# ETH_PCIE_PHY.net
KiCad netlist of a schematic drawn in Altium Designer
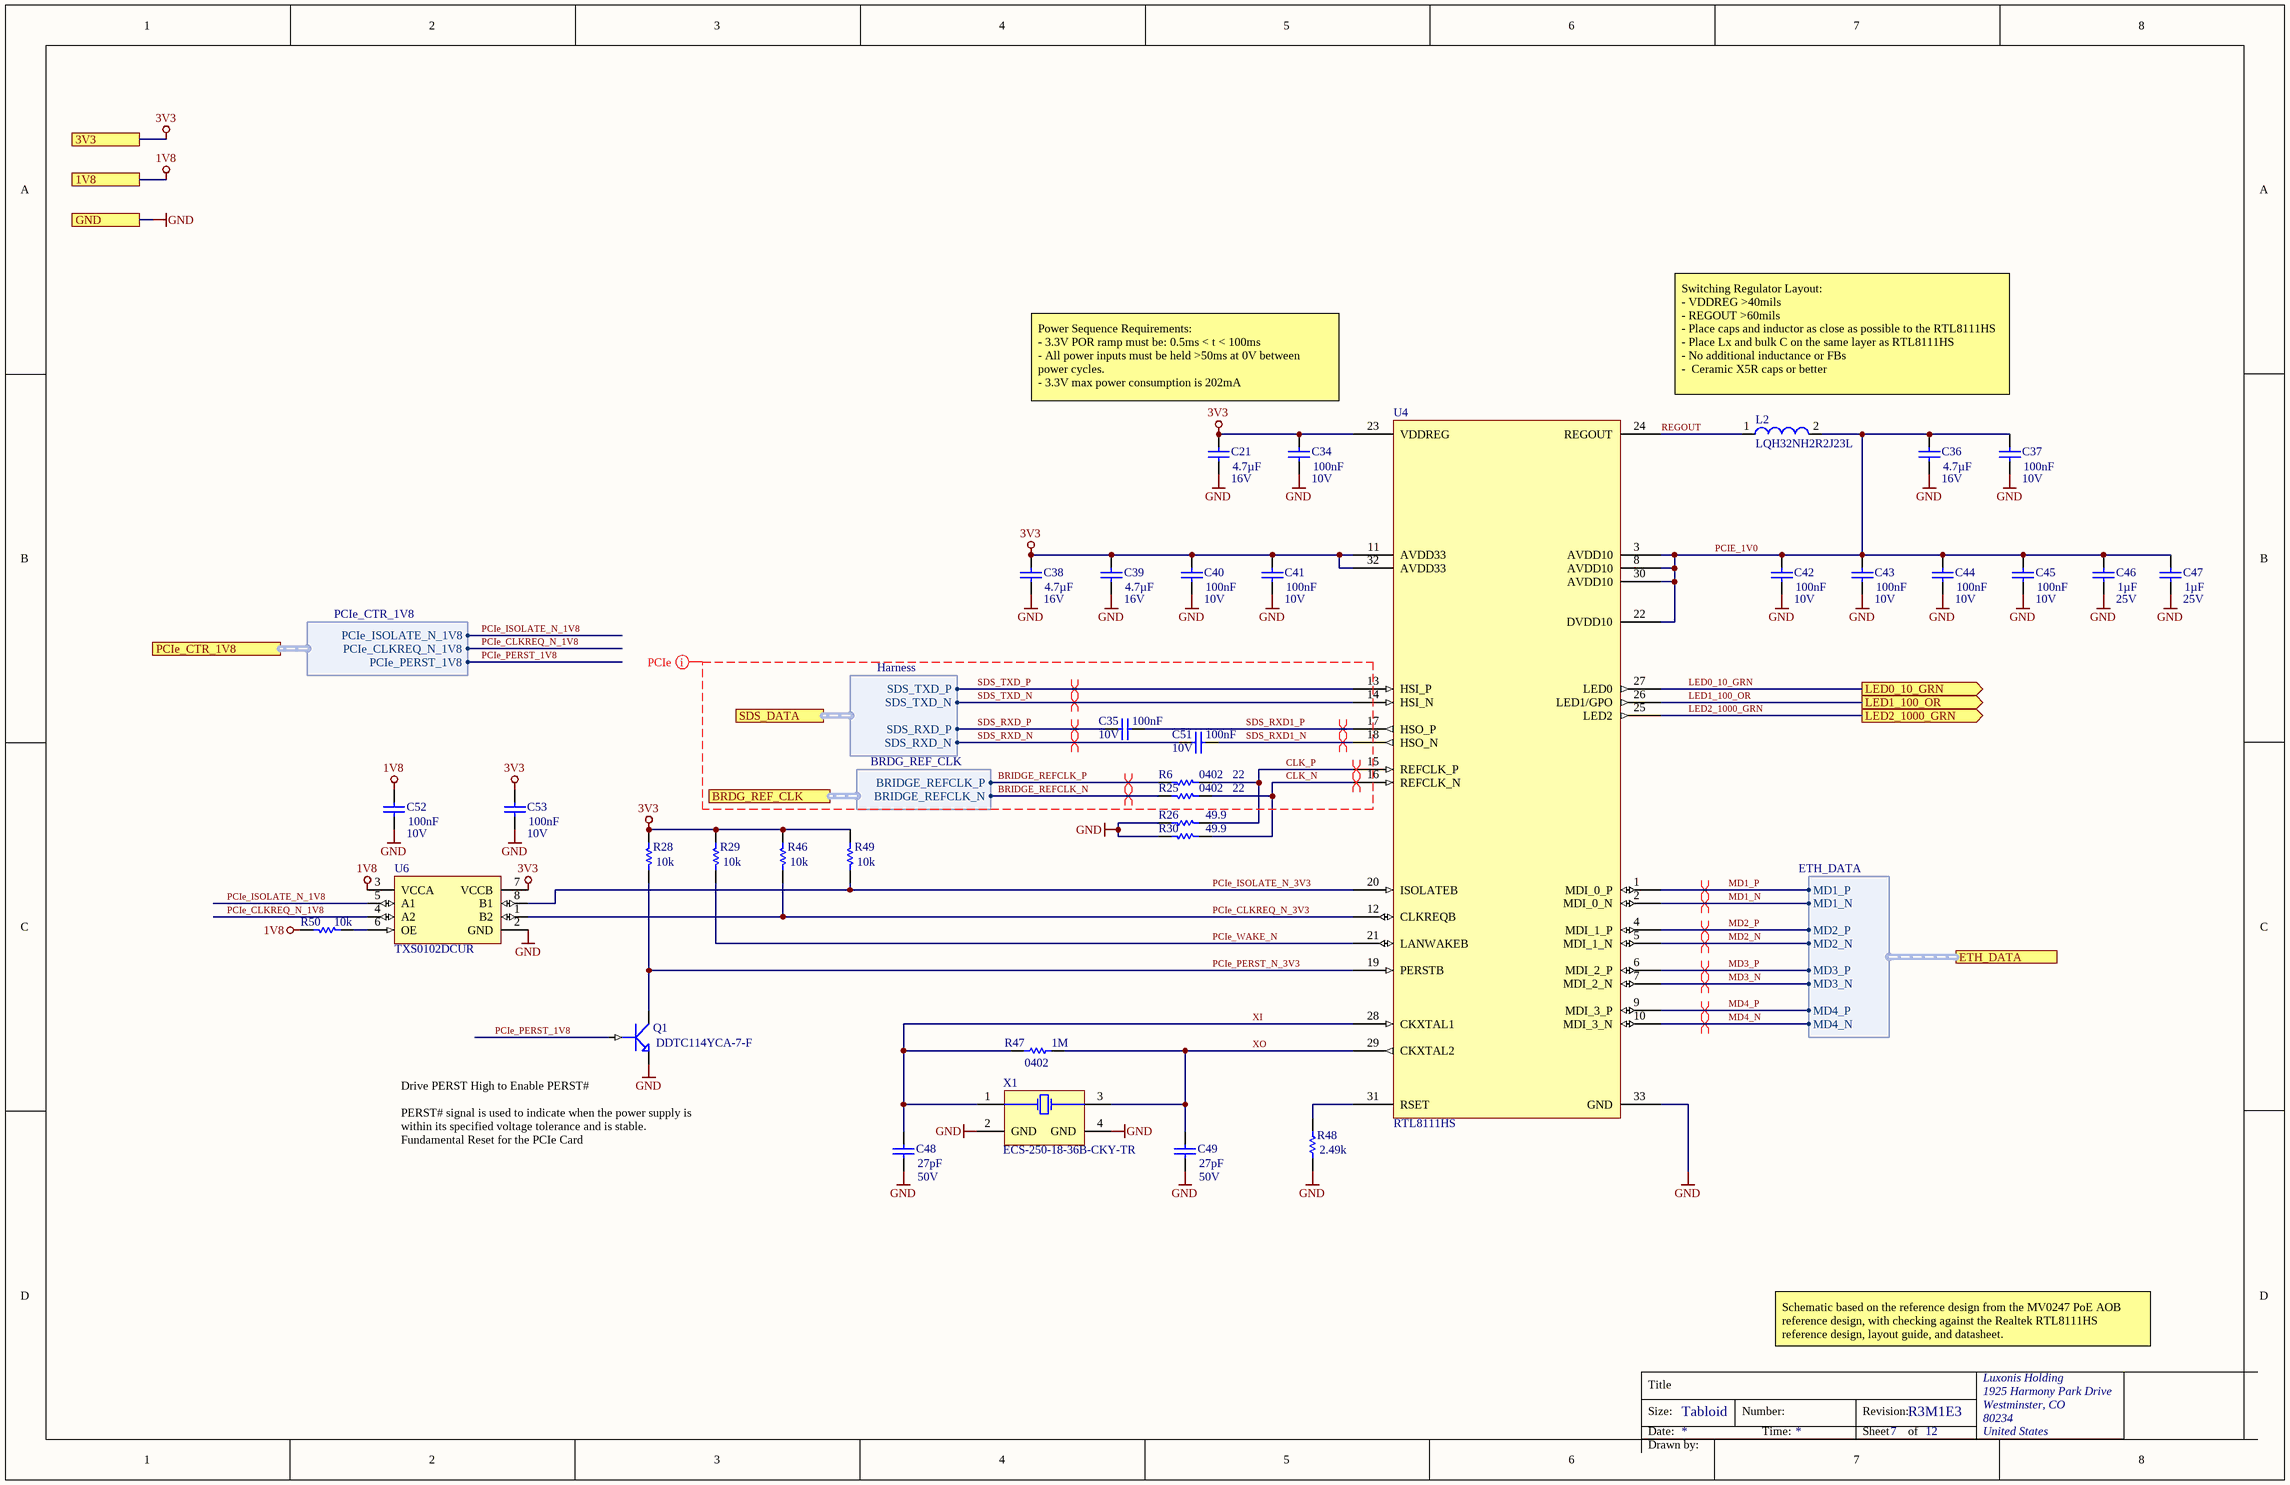
[diagram p0: ETH_PCIE_PHY.SchDoc]

(export (version "E")
  (design (tool "Eeschema 10.0.6"))
  (components
    (comp (ref "C21")
      (value "4.7µF")
      (footprint "CAPC0603(1608)100_N")
      (description "CAP CER 4.7UF 16V X5R 0603 10%")
      (fields
        (field (name "TOLERANCE") "10%")
        (field (name "VOLTAGE RATING") "16V")
        (field (name "Comment") "GRM188R61C475KAAJD")
      )
      (libsource (lib "Luxonis LLC") (part "LLL153C70G474ME17E"))
    )
    (comp (ref "C34")
      (value "100nF")
      (footprint "CAPC0402(1005)70_N")
      (description "CAP CER 0.1UF 10V X7R 0402 5%")
      (fields
        (field (name "TOLERANCE") "5%")
        (field (name "VOLTAGE RATING") "10V")
        (field (name "Comment") "GRM155R71A104JA01D")
      )
      (libsource (lib "Luxonis LLC") (part "GRM188R61C475KAAJD"))
    )
    (comp (ref "C35")
      (value "100nF")
      (footprint "CAPC0201(0603)33_L")
      (description "CAP CER 0.1UF 10V X5R 0201 10%")
      (fields
        (field (name "TOLERANCE") "10%")
        (field (name "VOLTAGE RATING") "10V")
        (field (name "Comment") "GRM033R61A104KE15D")
      )
      (libsource (lib "Luxonis LLC") (part "LLL153C70G474ME17E"))
    )
    (comp (ref "C36")
      (value "4.7µF")
      (footprint "CAPC0603(1608)100_N")
      (description "CAP CER 4.7UF 16V X5R 0603 10%")
      (fields
        (field (name "TOLERANCE") "10%")
        (field (name "VOLTAGE RATING") "16V")
        (field (name "Comment") "GRM188R61C475KAAJD")
      )
      (libsource (lib "Luxonis LLC") (part "LLL153C70G474ME17E"))
    )
    (comp (ref "C37")
      (value "100nF")
      (footprint "CAPC0402(1005)70_N")
      (description "CAP CER 0.1UF 10V X7R 0402 5%")
      (fields
        (field (name "TOLERANCE") "5%")
        (field (name "VOLTAGE RATING") "10V")
        (field (name "Comment") "GRM155R71A104JA01D")
      )
      (libsource (lib "Luxonis LLC") (part "GRM188R61C475KAAJD"))
    )
    (comp (ref "C38")
      (value "4.7µF")
      (footprint "CAPC0603(1608)100_N")
      (description "CAP CER 4.7UF 16V X5R 0603 10%")
      (fields
        (field (name "TOLERANCE") "10%")
        (field (name "VOLTAGE RATING") "16V")
        (field (name "Comment") "GRM188R61C475KAAJD")
      )
      (libsource (lib "Luxonis LLC") (part "LLL153C70G474ME17E"))
    )
    (comp (ref "C39")
      (value "4.7µF")
      (footprint "CAPC0603(1608)100_N")
      (description "CAP CER 4.7UF 16V X5R 0603 10%")
      (fields
        (field (name "TOLERANCE") "10%")
        (field (name "VOLTAGE RATING") "16V")
        (field (name "Comment") "GRM188R61C475KAAJD")
      )
      (libsource (lib "Luxonis LLC") (part "LLL153C70G474ME17E"))
    )
    (comp (ref "C40")
      (value "100nF")
      (footprint "CAPC0402(1005)70_N")
      (description "CAP CER 0.1UF 10V X7R 0402 5%")
      (fields
        (field (name "TOLERANCE") "5%")
        (field (name "VOLTAGE RATING") "10V")
        (field (name "Comment") "GRM155R71A104JA01D")
      )
      (libsource (lib "Luxonis LLC") (part "GRM188R61C475KAAJD"))
    )
    (comp (ref "C41")
      (value "100nF")
      (footprint "CAPC0402(1005)70_N")
      (description "CAP CER 0.1UF 10V X7R 0402 5%")
      (fields
        (field (name "TOLERANCE") "5%")
        (field (name "VOLTAGE RATING") "10V")
        (field (name "Comment") "GRM155R71A104JA01D")
      )
      (libsource (lib "Luxonis LLC") (part "GRM188R61C475KAAJD"))
    )
    (comp (ref "C42")
      (value "100nF")
      (footprint "CAPC0402(1005)70_N")
      (description "CAP CER 0.1UF 10V X7R 0402 5%")
      (fields
        (field (name "TOLERANCE") "5%")
        (field (name "VOLTAGE RATING") "10V")
        (field (name "Comment") "GRM155R71A104JA01D")
      )
      (libsource (lib "Luxonis LLC") (part "GRM188R61C475KAAJD"))
    )
    (comp (ref "C43")
      (value "100nF")
      (footprint "CAPC0402(1005)70_N")
      (description "CAP CER 0.1UF 10V X7R 0402 5%")
      (fields
        (field (name "TOLERANCE") "5%")
        (field (name "VOLTAGE RATING") "10V")
        (field (name "Comment") "GRM155R71A104JA01D")
      )
      (libsource (lib "Luxonis LLC") (part "GRM188R61C475KAAJD"))
    )
    (comp (ref "C44")
      (value "100nF")
      (footprint "CAPC0402(1005)70_N")
      (description "CAP CER 0.1UF 10V X7R 0402 5%")
      (fields
        (field (name "TOLERANCE") "5%")
        (field (name "VOLTAGE RATING") "10V")
        (field (name "Comment") "GRM155R71A104JA01D")
      )
      (libsource (lib "Luxonis LLC") (part "GRM188R61C475KAAJD"))
    )
    (comp (ref "C45")
      (value "100nF")
      (footprint "CAPC0402(1005)70_N")
      (description "CAP CER 0.1UF 10V X7R 0402 5%")
      (fields
        (field (name "TOLERANCE") "5%")
        (field (name "VOLTAGE RATING") "10V")
        (field (name "Comment") "GRM155R71A104JA01D")
      )
      (libsource (lib "Luxonis LLC") (part "GRM188R61C475KAAJD"))
    )
    (comp (ref "C46")
      (value "1µF")
      (footprint "CAPC0402(1005)70_N")
      (description "CAP CER 1UF 25V X5R 0402 10%")
      (fields
        (field (name "TOLERANCE") "10%")
        (field (name "VOLTAGE RATING") "25V")
        (field (name "Comment") "GRM155R61E105KA12D")
      )
      (libsource (lib "Luxonis LLC") (part "GRM188R61C475KAAJD"))
    )
    (comp (ref "C47")
      (value "1µF")
      (footprint "CAPC0402(1005)70_N")
      (description "CAP CER 1UF 25V X5R 0402 10%")
      (fields
        (field (name "TOLERANCE") "10%")
        (field (name "VOLTAGE RATING") "25V")
        (field (name "Comment") "GRM155R61E105KA12D")
      )
      (libsource (lib "Luxonis LLC") (part "GRM188R61C475KAAJD"))
    )
    (comp (ref "C48")
      (value "27pF")
      (footprint "CAPC0402(1005)60_N")
      (description "CAP CER 27PF 50V C0G 0402 5%")
      (fields
        (field (name "TOLERANCE") "5%")
        (field (name "VOLTAGE RATING") "50V")
        (field (name "Comment") "C0402C270J5GACTU")
      )
      (libsource (lib "Luxonis LLC") (part "GRM188R61C475KAAJD"))
    )
    (comp (ref "C49")
      (value "27pF")
      (footprint "CAPC0402(1005)60_N")
      (description "CAP CER 27PF 50V C0G 0402 5%")
      (fields
        (field (name "TOLERANCE") "5%")
        (field (name "VOLTAGE RATING") "50V")
        (field (name "Comment") "C0402C270J5GACTU")
      )
      (libsource (lib "Luxonis LLC") (part "GRM188R61C475KAAJD"))
    )
    (comp (ref "C51")
      (value "100nF")
      (footprint "CAPC0201(0603)33_L")
      (description "CAP CER 0.1UF 10V X5R 0201 10%")
      (fields
        (field (name "TOLERANCE") "10%")
        (field (name "VOLTAGE RATING") "10V")
        (field (name "Comment") "GRM033R61A104KE15D")
      )
      (libsource (lib "Luxonis LLC") (part "LLL153C70G474ME17E"))
    )
    (comp (ref "C52")
      (value "100nF")
      (footprint "CAPC0402(1005)70_N")
      (description "CAP CER 0.1UF 10V X7R 0402 5%")
      (fields
        (field (name "TOLERANCE") "5%")
        (field (name "VOLTAGE RATING") "10V")
        (field (name "Comment") "GRM155R71A104JA01D")
      )
      (libsource (lib "Luxonis LLC") (part "GRM188R61C475KAAJD"))
    )
    (comp (ref "C53")
      (value "100nF")
      (footprint "CAPC0402(1005)70_N")
      (description "CAP CER 0.1UF 10V X7R 0402 5%")
      (fields
        (field (name "TOLERANCE") "5%")
        (field (name "VOLTAGE RATING") "10V")
        (field (name "Comment") "GRM155R71A104JA01D")
      )
      (libsource (lib "Luxonis LLC") (part "GRM188R61C475KAAJD"))
    )
    (comp (ref "L2")
      (value "LQH32NH2R2J23L")
      (footprint "LQH32NH2R2J23L")
      (description "FIXED IND 2.2UH 610MA 97MOHM SMD")
      (fields (field (name "TOLERANCE") "5%"))
      (libsource (lib "Luxonis LLC") (part "DFE252012P-1R0M=P2"))
    )
    (comp (ref "Q1")
      (value "DDTC114YCA-7-F")
      (footprint "DDTC114YCA-7-F-Footprint-1")
      (description "TRANS PREBIAS NPN 200MW SOT23-3")
      (libsource (lib "Luxonis LLC") (part "DDTC114YCA-7-F"))
    )
    (comp (ref "R6")
      (value "22")
      (footprint "RESC0402(1005)_L")
      (description "RES SMD 22 OHM 1% 1/16W 0402")
      (fields
        (field (name "CASE/PACKAGE") "0402")
        (field (name "TOLERANCE") "1%")
        (field (name "Comment") "RC0402FR-0722RL")
      )
      (libsource (lib "Luxonis LLC") (part "Default resistor symbol"))
    )
    (comp (ref "R25")
      (value "22")
      (footprint "RESC0402(1005)_L")
      (description "RES SMD 22 OHM 1% 1/16W 0402")
      (fields
        (field (name "CASE/PACKAGE") "0402")
        (field (name "TOLERANCE") "1%")
        (field (name "Comment") "RC0402FR-0722RL")
      )
      (libsource (lib "Luxonis LLC") (part "Default resistor symbol"))
    )
    (comp (ref "R26")
      (value "49.9")
      (footprint "RESC0402(1005)_L")
      (description "RES SMD 49.9 OHM 1% 1/16W 0402")
      (fields (field (name "TOLERANCE") "1%") (field (name "Comment") "RC0402FR-0749R9L"))
      (libsource (lib "Luxonis LLC") (part "RC0402FR-0722RL_1"))
    )
    (comp (ref "R28")
      (value "10k")
      (footprint "RESC0402(1005)_N")
      (description "RES SMD 10K OHM 1% 1/16W 0402")
      (fields (field (name "TOLERANCE") "1%") (field (name "Comment") "RC0402FR-1310KL"))
      (libsource (lib "Luxonis LLC") (part "RC0402FR-0722RL_1"))
    )
    (comp (ref "R29")
      (value "10k")
      (footprint "RESC0402(1005)_N")
      (description "RES SMD 10K OHM 1% 1/16W 0402")
      (fields (field (name "TOLERANCE") "1%") (field (name "Comment") "RC0402FR-1310KL"))
      (libsource (lib "Luxonis LLC") (part "RC0402FR-0722RL_1"))
    )
    (comp (ref "R30")
      (value "49.9")
      (footprint "RESC0402(1005)_L")
      (description "RES SMD 49.9 OHM 1% 1/16W 0402")
      (fields (field (name "TOLERANCE") "1%") (field (name "Comment") "RC0402FR-0749R9L"))
      (libsource (lib "Luxonis LLC") (part "RC0402FR-0722RL_1"))
    )
    (comp (ref "R46")
      (value "10k")
      (footprint "RESC0402(1005)_N")
      (description "RES SMD 10K OHM 1% 1/16W 0402")
      (fields (field (name "TOLERANCE") "1%") (field (name "Comment") "RC0402FR-1310KL"))
      (libsource (lib "Luxonis LLC") (part "RC0402FR-0722RL_1"))
    )
    (comp (ref "R47")
      (value "1M")
      (footprint "RESC0402(1005)_N")
      (description "RES SMD 1M OHM 1% 1/16W 0402")
      (fields
        (field (name "CASE/PACKAGE") "0402")
        (field (name "TOLERANCE") "1%")
        (field (name "Comment") "RC0402FR-071ML")
      )
      (libsource (lib "Luxonis LLC") (part "Default resistor symbol"))
    )
    (comp (ref "R48")
      (value "2.49k")
      (footprint "RESC0402(1005)_N")
      (description "RES SMD 2.49K OHM 1% 1/16W 0402")
      (fields (field (name "TOLERANCE") "1%") (field (name "Comment") "RC0402FR-072K49L"))
      (libsource (lib "Luxonis LLC") (part "RC0402FR-0722RL_1"))
    )
    (comp (ref "R49")
      (value "10k")
      (footprint "RESC0402(1005)_N")
      (description "RES SMD 10K OHM 1% 1/16W 0402")
      (fields (field (name "TOLERANCE") "1%") (field (name "Comment") "RC0402FR-1310KL"))
      (libsource (lib "Luxonis LLC") (part "RC0402FR-0722RL_1"))
    )
    (comp (ref "R50")
      (value "10k")
      (footprint "RESC0402(1005)_N")
      (description "RES SMD 10K OHM 1% 1/16W 0402")
      (fields (field (name "TOLERANCE") "1%") (field (name "Comment") "RC0402FR-1310KL"))
      (libsource (lib "Luxonis LLC") (part "RC0402FR-0722RL_1"))
    )
    (comp (ref "U4")
      (value "RTL8111HS")
      (footprint "RTL8111Hx-CG")
      (description "IC ETHERNET/PCIe PHY Realtek")
      (libsource (lib "Luxonis LLC") (part "RTL8111HS"))
    )
    (comp (ref "U6")
      (value "TXS0102DCUR")
      (footprint "TXS0102DCUR")
      (description "TEXAS INSTRUMENTS - TXS0102DCUR - IC, TRANSLATOR, 2 BIT, BI, US-8")
      (libsource (lib "Luxonis LLC") (part "TXS0102DCUR"))
    )
    (comp (ref "X1")
      (value "ECS-250-18-36B-CKY-TR")
      (footprint "ECS-250-18-36B-CKY-TR")
      (description "CRYSTAL 25.0000MHZ 18PF SMD 25MHz ±10ppm Crystal 18pF 50 Ohms 4-SMD, No Lead")
      (libsource (lib "Luxonis LLC") (part "ECS-250-18-36B-CKY-TR"))
    )
  )
  (nets
    (net (code "5") (name "/BRIDGE_REFCLK_N") (class "Default")
      (node (ref "R25") (pin "2") (pinfunction "2_2") (pintype "passive"))
    )
    (net (code "6") (name "/BRIDGE_REFCLK_P") (class "Default")
      (node (ref "R6") (pin "2") (pinfunction "2_2") (pintype "passive"))
    )
    (net (code "7") (name "/CLK_N") (class "Default")
      (node (ref "R25") (pin "1") (pinfunction "1_1") (pintype "passive"))
      (node (ref "R30") (pin "2") (pinfunction "2_2") (pintype "passive"))
      (node (ref "U4") (pin "16") (pinfunction "REFCLK_N_16") (pintype "input"))
    )
    (net (code "8") (name "/CLK_P") (class "Default")
      (node (ref "R26") (pin "2") (pinfunction "2_2") (pintype "passive"))
      (node (ref "R6") (pin "1") (pinfunction "1_1") (pintype "passive"))
      (node (ref "U4") (pin "15") (pinfunction "REFCLK_P_15") (pintype "input"))
    )
    (net (code "9") (name "/LED0_10_GRN") (class "Default")
      (node (ref "U4") (pin "27") (pinfunction "LED0_27") (pintype "output"))
    )
    (net (code "10") (name "/LED1_100_OR") (class "Default")
      (node (ref "U4") (pin "26") (pinfunction "LED1/GPO_26") (pintype "output"))
    )
    (net (code "11") (name "/LED2_1000_GRN") (class "Default")
      (node (ref "U4") (pin "25") (pinfunction "LED2_25") (pintype "output"))
    )
    (net (code "12") (name "/MD1_N") (class "Default")
      (node (ref "U4") (pin "2") (pinfunction "MDI_0_N_2") (pintype "bidirectional"))
    )
    (net (code "13") (name "/MD1_P") (class "Default")
      (node (ref "U4") (pin "1") (pinfunction "MDI_0_P_1") (pintype "bidirectional"))
    )
    (net (code "14") (name "/MD2_N") (class "Default")
      (node (ref "U4") (pin "5") (pinfunction "MDI_1_N_5") (pintype "bidirectional"))
    )
    (net (code "15") (name "/MD2_P") (class "Default")
      (node (ref "U4") (pin "4") (pinfunction "MDI_1_P_4") (pintype "bidirectional"))
    )
    (net (code "16") (name "/MD3_N") (class "Default")
      (node (ref "U4") (pin "7") (pinfunction "MDI_2_N_7") (pintype "bidirectional"))
    )
    (net (code "17") (name "/MD3_P") (class "Default")
      (node (ref "U4") (pin "6") (pinfunction "MDI_2_P_6") (pintype "bidirectional"))
    )
    (net (code "18") (name "/MD4_N") (class "Default")
      (node (ref "U4") (pin "10") (pinfunction "MDI_3_N_10") (pintype "bidirectional"))
    )
    (net (code "19") (name "/MD4_P") (class "Default")
      (node (ref "U4") (pin "9") (pinfunction "MDI_3_P_9") (pintype "bidirectional"))
    )
    (net (code "20") (name "/PCIE_1V0") (class "Default")
      (node (ref "C36") (pin "2") (pinfunction "2_2") (pintype "passive"))
      (node (ref "C37") (pin "2") (pinfunction "2_2") (pintype "passive"))
      (node (ref "C42") (pin "2") (pinfunction "2_2") (pintype "passive"))
      (node (ref "C43") (pin "2") (pinfunction "2_2") (pintype "passive"))
      (node (ref "C44") (pin "2") (pinfunction "2_2") (pintype "passive"))
      (node (ref "C45") (pin "2") (pinfunction "2_2") (pintype "passive"))
      (node (ref "C46") (pin "2") (pinfunction "2_2") (pintype "passive"))
      (node (ref "C47") (pin "2") (pinfunction "2_2") (pintype "passive"))
      (node (ref "L2") (pin "2") (pinfunction "2_2") (pintype "passive"))
      (node (ref "U4") (pin "22") (pinfunction "DVDD10_22") (pintype "passive"))
      (node (ref "U4") (pin "3") (pinfunction "AVDD10_3") (pintype "passive"))
      (node (ref "U4") (pin "30") (pinfunction "AVDD10_30") (pintype "passive"))
      (node (ref "U4") (pin "8") (pinfunction "AVDD10_8") (pintype "passive"))
    )
    (net (code "21") (name "/PCIe_CLKREQ_N_1V8") (class "Default")
      (node (ref "U6") (pin "4") (pinfunction "A2_4") (pintype "bidirectional"))
    )
    (net (code "22") (name "/PCIe_CLKREQ_N_3V3") (class "Default")
      (node (ref "R46") (pin "2") (pinfunction "2_2") (pintype "passive"))
      (node (ref "U4") (pin "12") (pinfunction "CLKREQB_12") (pintype "bidirectional"))
      (node (ref "U6") (pin "1") (pinfunction "B2_1") (pintype "bidirectional"))
    )
    (net (code "23") (name "/PCIe_ISOLATE_N_1V8") (class "Default")
      (node (ref "U6") (pin "5") (pinfunction "A1_5") (pintype "bidirectional"))
    )
    (net (code "24") (name "/PCIe_ISOLATE_N_3V3") (class "Default")
      (node (ref "R49") (pin "2") (pinfunction "2_2") (pintype "passive"))
      (node (ref "U4") (pin "20") (pinfunction "ISOLATEB_20") (pintype "input"))
      (node (ref "U6") (pin "8") (pinfunction "B1_8") (pintype "bidirectional"))
    )
    (net (code "25") (name "/PCIe_PERST_1V8") (class "Default")
      (node (ref "Q1") (pin "1") (pinfunction "B_1") (pintype "input"))
    )
    (net (code "26") (name "/PCIe_PERST_N_3V3") (class "Default")
      (node (ref "Q1") (pin "3") (pinfunction "C_3") (pintype "passive"))
      (node (ref "R28") (pin "2") (pinfunction "2_2") (pintype "passive"))
      (node (ref "U4") (pin "19") (pinfunction "PERSTB_19") (pintype "input"))
    )
    (net (code "27") (name "/PCIe_WAKE_N") (class "Default")
      (node (ref "R29") (pin "2") (pinfunction "2_2") (pintype "passive"))
      (node (ref "U4") (pin "21") (pinfunction "LANWAKEB_21") (pintype "bidirectional"))
    )
    (net (code "28") (name "/REGOUT") (class "Default")
      (node (ref "L2") (pin "1") (pinfunction "1_1") (pintype "passive"))
      (node (ref "U4") (pin "24") (pinfunction "REGOUT_24") (pintype "passive"))
    )
    (net (code "29") (name "/SDS_RXD1_N") (class "Default")
      (node (ref "C51") (pin "2") (pinfunction "2_2") (pintype "passive"))
      (node (ref "U4") (pin "18") (pinfunction "HSO_N_18") (pintype "output"))
    )
    (net (code "30") (name "/SDS_RXD1_P") (class "Default")
      (node (ref "C35") (pin "2") (pinfunction "2_2") (pintype "passive"))
      (node (ref "U4") (pin "17") (pinfunction "HSO_P_17") (pintype "output"))
    )
    (net (code "31") (name "/SDS_RXD_N") (class "Default")
      (node (ref "C51") (pin "1") (pinfunction "1_1") (pintype "passive"))
    )
    (net (code "32") (name "/SDS_RXD_P") (class "Default")
      (node (ref "C35") (pin "1") (pinfunction "1_1") (pintype "passive"))
    )
    (net (code "33") (name "/SDS_TXD_N") (class "Default")
      (node (ref "U4") (pin "14") (pinfunction "HSI_N_14") (pintype "input"))
    )
    (net (code "34") (name "/SDS_TXD_P") (class "Default")
      (node (ref "U4") (pin "13") (pinfunction "HSI_P_13") (pintype "input"))
    )
    (net (code "35") (name "/XI") (class "Default")
      (node (ref "C48") (pin "2") (pinfunction "2_2") (pintype "passive"))
      (node (ref "R47") (pin "1") (pinfunction "1_1") (pintype "passive"))
      (node (ref "U4") (pin "28") (pinfunction "CKXTAL1_28") (pintype "input"))
      (node (ref "X1") (pin "1") (pinfunction "X1_1") (pintype "passive"))
    )
    (net (code "36") (name "/XO") (class "Default")
      (node (ref "C49") (pin "2") (pinfunction "2_2") (pintype "passive"))
      (node (ref "R47") (pin "2") (pinfunction "2_2") (pintype "passive"))
      (node (ref "U4") (pin "29") (pinfunction "CKXTAL2_29") (pintype "output"))
      (node (ref "X1") (pin "3") (pinfunction "X2_3") (pintype "passive"))
    )
    (net (code "41") (name "1V8") (class "Default")
      (node (ref "C52") (pin "2") (pinfunction "2_2") (pintype "passive"))
      (node (ref "R50") (pin "2") (pinfunction "2_2") (pintype "passive"))
      (node (ref "U6") (pin "3") (pinfunction "VCCA_3") (pintype "power_in"))
    )
    (net (code "42") (name "3V3") (class "Default")
      (node (ref "C21") (pin "2") (pinfunction "2_2") (pintype "passive"))
      (node (ref "C34") (pin "2") (pinfunction "2_2") (pintype "passive"))
      (node (ref "C38") (pin "2") (pinfunction "2_2") (pintype "passive"))
      (node (ref "C39") (pin "2") (pinfunction "2_2") (pintype "passive"))
      (node (ref "C40") (pin "2") (pinfunction "2_2") (pintype "passive"))
      (node (ref "C41") (pin "2") (pinfunction "2_2") (pintype "passive"))
      (node (ref "C53") (pin "2") (pinfunction "2_2") (pintype "passive"))
      (node (ref "R28") (pin "1") (pinfunction "1_1") (pintype "passive"))
      (node (ref "R29") (pin "1") (pinfunction "1_1") (pintype "passive"))
      (node (ref "R46") (pin "1") (pinfunction "1_1") (pintype "passive"))
      (node (ref "R49") (pin "1") (pinfunction "1_1") (pintype "passive"))
      (node (ref "U4") (pin "11") (pinfunction "AVDD33_11") (pintype "passive"))
      (node (ref "U4") (pin "23") (pinfunction "VDDREG_23") (pintype "passive"))
      (node (ref "U4") (pin "32") (pinfunction "AVDD33_32") (pintype "passive"))
      (node (ref "U6") (pin "7") (pinfunction "VCCB_7") (pintype "power_in"))
    )
    (net (code "43") (name "GND") (class "Default")
      (node (ref "C21") (pin "1") (pinfunction "1_1") (pintype "passive"))
      (node (ref "C34") (pin "1") (pinfunction "1_1") (pintype "passive"))
      (node (ref "C36") (pin "1") (pinfunction "1_1") (pintype "passive"))
      (node (ref "C37") (pin "1") (pinfunction "1_1") (pintype "passive"))
      (node (ref "C38") (pin "1") (pinfunction "1_1") (pintype "passive"))
      (node (ref "C39") (pin "1") (pinfunction "1_1") (pintype "passive"))
      (node (ref "C40") (pin "1") (pinfunction "1_1") (pintype "passive"))
      (node (ref "C41") (pin "1") (pinfunction "1_1") (pintype "passive"))
      (node (ref "C42") (pin "1") (pinfunction "1_1") (pintype "passive"))
      (node (ref "C43") (pin "1") (pinfunction "1_1") (pintype "passive"))
      (node (ref "C44") (pin "1") (pinfunction "1_1") (pintype "passive"))
      (node (ref "C45") (pin "1") (pinfunction "1_1") (pintype "passive"))
      (node (ref "C46") (pin "1") (pinfunction "1_1") (pintype "passive"))
      (node (ref "C47") (pin "1") (pinfunction "1_1") (pintype "passive"))
      (node (ref "C48") (pin "1") (pinfunction "1_1") (pintype "passive"))
      (node (ref "C49") (pin "1") (pinfunction "1_1") (pintype "passive"))
      (node (ref "C52") (pin "1") (pinfunction "1_1") (pintype "passive"))
      (node (ref "C53") (pin "1") (pinfunction "1_1") (pintype "passive"))
      (node (ref "Q1") (pin "2") (pinfunction "E_2") (pintype "passive"))
      (node (ref "R26") (pin "1") (pinfunction "1_1") (pintype "passive"))
      (node (ref "R30") (pin "1") (pinfunction "1_1") (pintype "passive"))
      (node (ref "R48") (pin "1") (pinfunction "1_1") (pintype "passive"))
      (node (ref "U4") (pin "33") (pinfunction "GND_33") (pintype "passive"))
      (node (ref "U6") (pin "2") (pinfunction "GND_2") (pintype "power_in"))
      (node (ref "X1") (pin "2") (pinfunction "GND_2") (pintype "power_in"))
      (node (ref "X1") (pin "4") (pinfunction "GND_4") (pintype "power_in"))
    )
    (net (code "44") (name "Net-(U4-RSET)") (class "Default")
      (node (ref "R48") (pin "2") (pinfunction "2_2") (pintype "passive"))
      (node (ref "U4") (pin "31") (pinfunction "RSET_31") (pintype "passive"))
    )
    (net (code "45") (name "Net-(U6-OE)") (class "Default")
      (node (ref "R50") (pin "1") (pinfunction "1_1") (pintype "passive"))
      (node (ref "U6") (pin "6") (pinfunction "OE_6") (pintype "input"))
    )
  )
)
